# Reflect.net
KiCad netlist of a schematic drawn in EAGLE
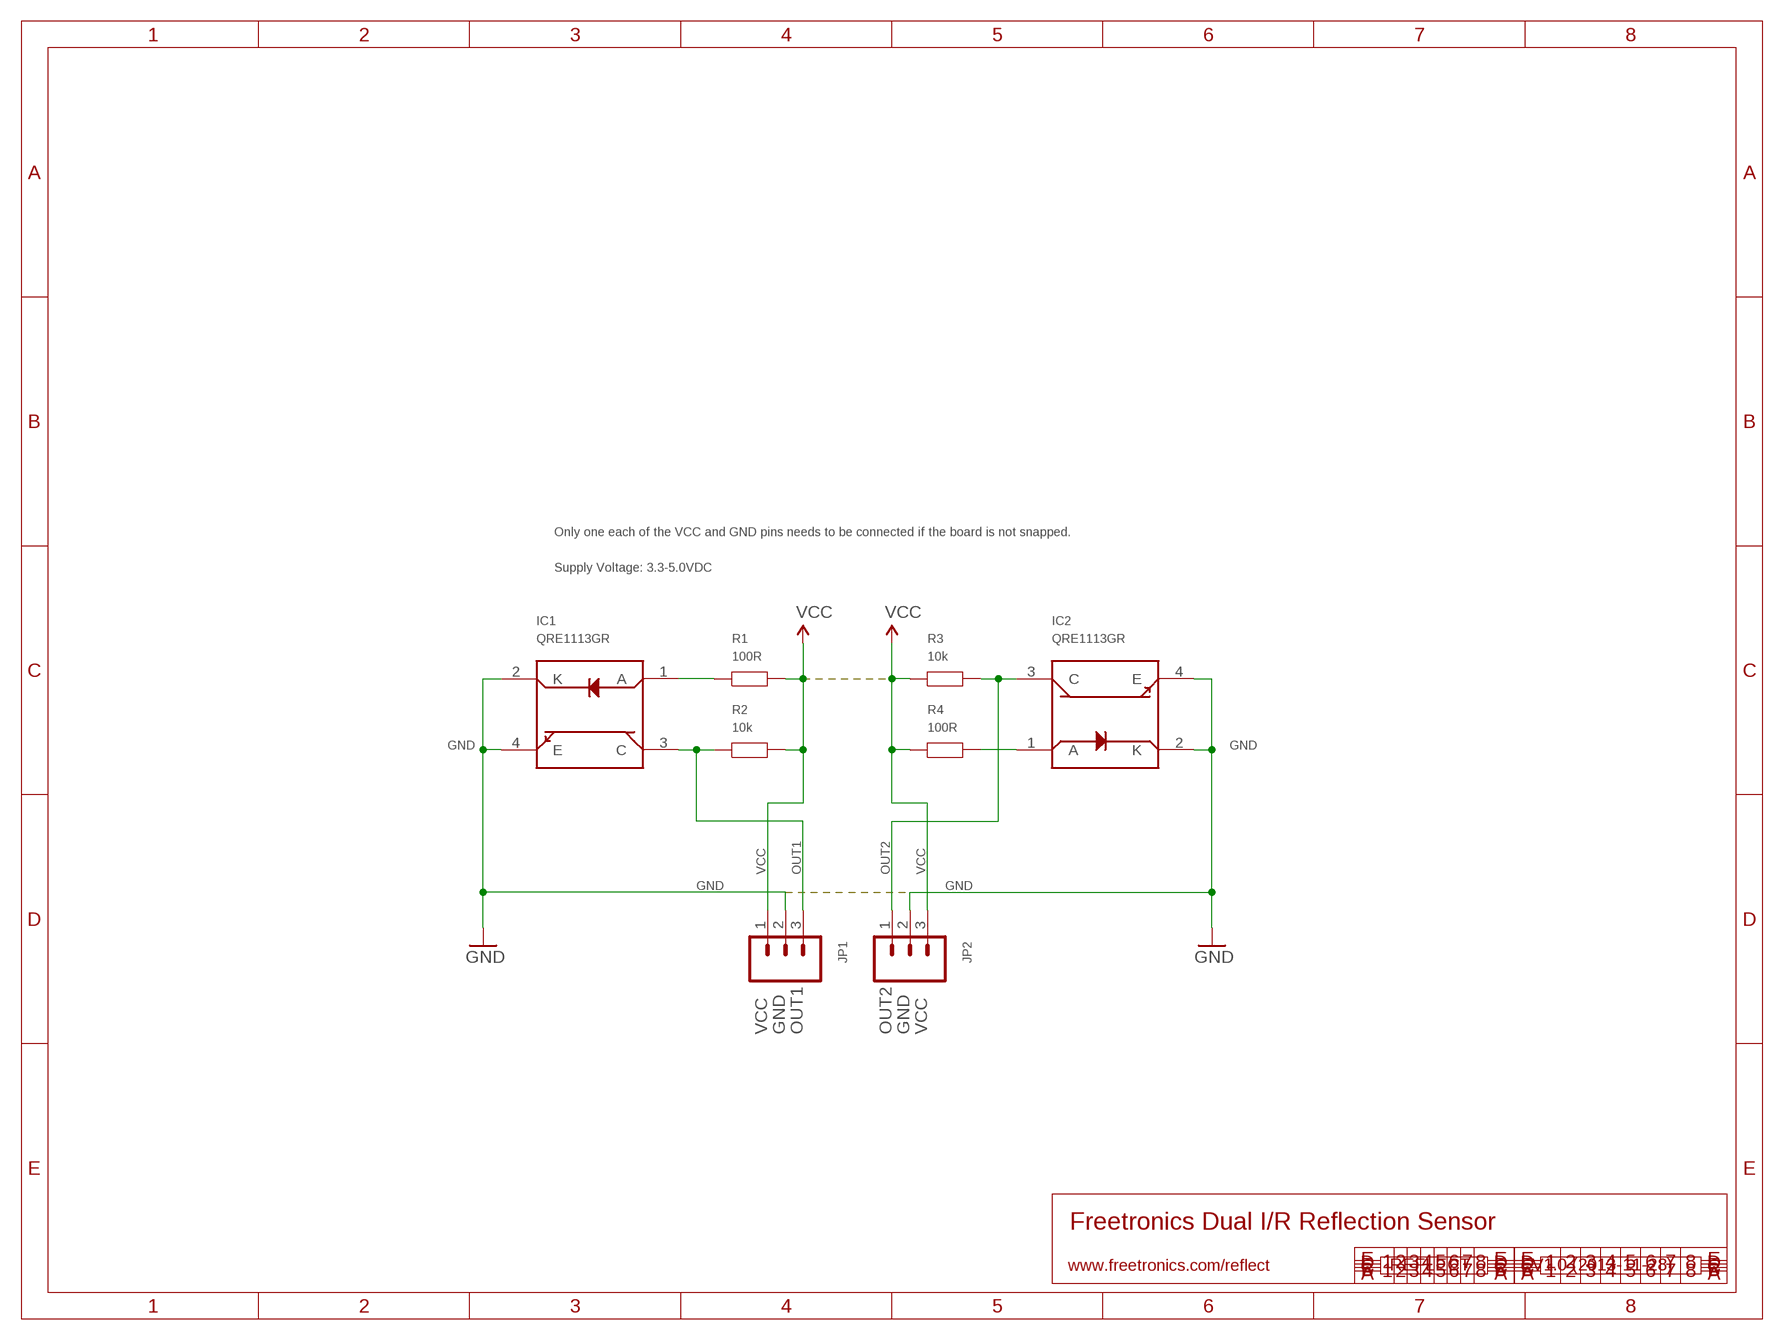
[diagram p0: schematic, sheet 1]

(export (version "E")
  (design (tool "Eeschema 10.0.6"))
  (components
    (comp (ref "IC1")
      (value "QRE1113GR")
      (footprint "eagle-import:QRE1113GR")
      (libsource (lib "eagle-import") (part "QRE1113GR"))
    )
    (comp (ref "IC2")
      (value "QRE1113GR")
      (footprint "eagle-import:QRE1113GR")
      (libsource (lib "eagle-import") (part "QRE1113GR"))
    )
    (comp (ref "JP1")
      (value "M03PTH")
      (footprint "eagle-import:1X03")
      (libsource (lib "eagle-import") (part "M03PTH"))
    )
    (comp (ref "JP2")
      (value "M03PTH")
      (footprint "eagle-import:1X03")
      (libsource (lib "eagle-import") (part "M03PTH"))
    )
    (comp (ref "R1")
      (value "100R")
      (footprint "eagle-import:0603")
      (libsource (lib "eagle-import") (part "RESISTOR0603"))
    )
    (comp (ref "R2")
      (value "10k")
      (footprint "eagle-import:0603")
      (libsource (lib "eagle-import") (part "RESISTOR0603"))
    )
    (comp (ref "R3")
      (value "10k")
      (footprint "eagle-import:0603")
      (libsource (lib "eagle-import") (part "RESISTOR0603"))
    )
    (comp (ref "R4")
      (value "100R")
      (footprint "eagle-import:0603")
      (libsource (lib "eagle-import") (part "RESISTOR0603"))
    )
  )
  (nets
    (net (code "1") (name "/OUT1") (class "Default")
      (node (ref "IC1") (pin "3") (pinfunction "C_3") (pintype "input"))
      (node (ref "JP1") (pin "3") (pinfunction "3_3") (pintype "passive"))
      (node (ref "R2") (pin "1") (pinfunction "1_1") (pintype "passive"))
    )
    (net (code "2") (name "/OUT2") (class "Default")
      (node (ref "IC2") (pin "3") (pinfunction "C_3") (pintype "input"))
      (node (ref "JP2") (pin "1") (pinfunction "1_1") (pintype "passive"))
      (node (ref "R3") (pin "2") (pinfunction "2_2") (pintype "passive"))
    )
    (net (code "3") (name "GND") (class "Default")
      (node (ref "IC1") (pin "2") (pinfunction "K_2") (pintype "input"))
      (node (ref "IC1") (pin "4") (pinfunction "E_4") (pintype "input"))
      (node (ref "IC2") (pin "2") (pinfunction "K_2") (pintype "input"))
      (node (ref "IC2") (pin "4") (pinfunction "E_4") (pintype "input"))
      (node (ref "JP1") (pin "2") (pinfunction "2_2") (pintype "passive"))
      (node (ref "JP2") (pin "2") (pinfunction "2_2") (pintype "passive"))
    )
    (net (code "4") (name "Net-(IC1-A)") (class "Default")
      (node (ref "IC1") (pin "1") (pinfunction "A_1") (pintype "input"))
      (node (ref "R1") (pin "1") (pinfunction "1_1") (pintype "passive"))
    )
    (net (code "5") (name "Net-(IC2-A)") (class "Default")
      (node (ref "IC2") (pin "1") (pinfunction "A_1") (pintype "input"))
      (node (ref "R4") (pin "2") (pinfunction "2_2") (pintype "passive"))
    )
    (net (code "6") (name "VCC") (class "Default")
      (node (ref "JP1") (pin "1") (pinfunction "1_1") (pintype "passive"))
      (node (ref "JP2") (pin "3") (pinfunction "3_3") (pintype "passive"))
      (node (ref "R1") (pin "2") (pinfunction "2_2") (pintype "passive"))
      (node (ref "R2") (pin "2") (pinfunction "2_2") (pintype "passive"))
      (node (ref "R3") (pin "1") (pinfunction "1_1") (pintype "passive"))
      (node (ref "R4") (pin "1") (pinfunction "1_1") (pintype "passive"))
    )
  )
)
